# subd.net
KiCad netlist of a schematic drawn in EAGLE
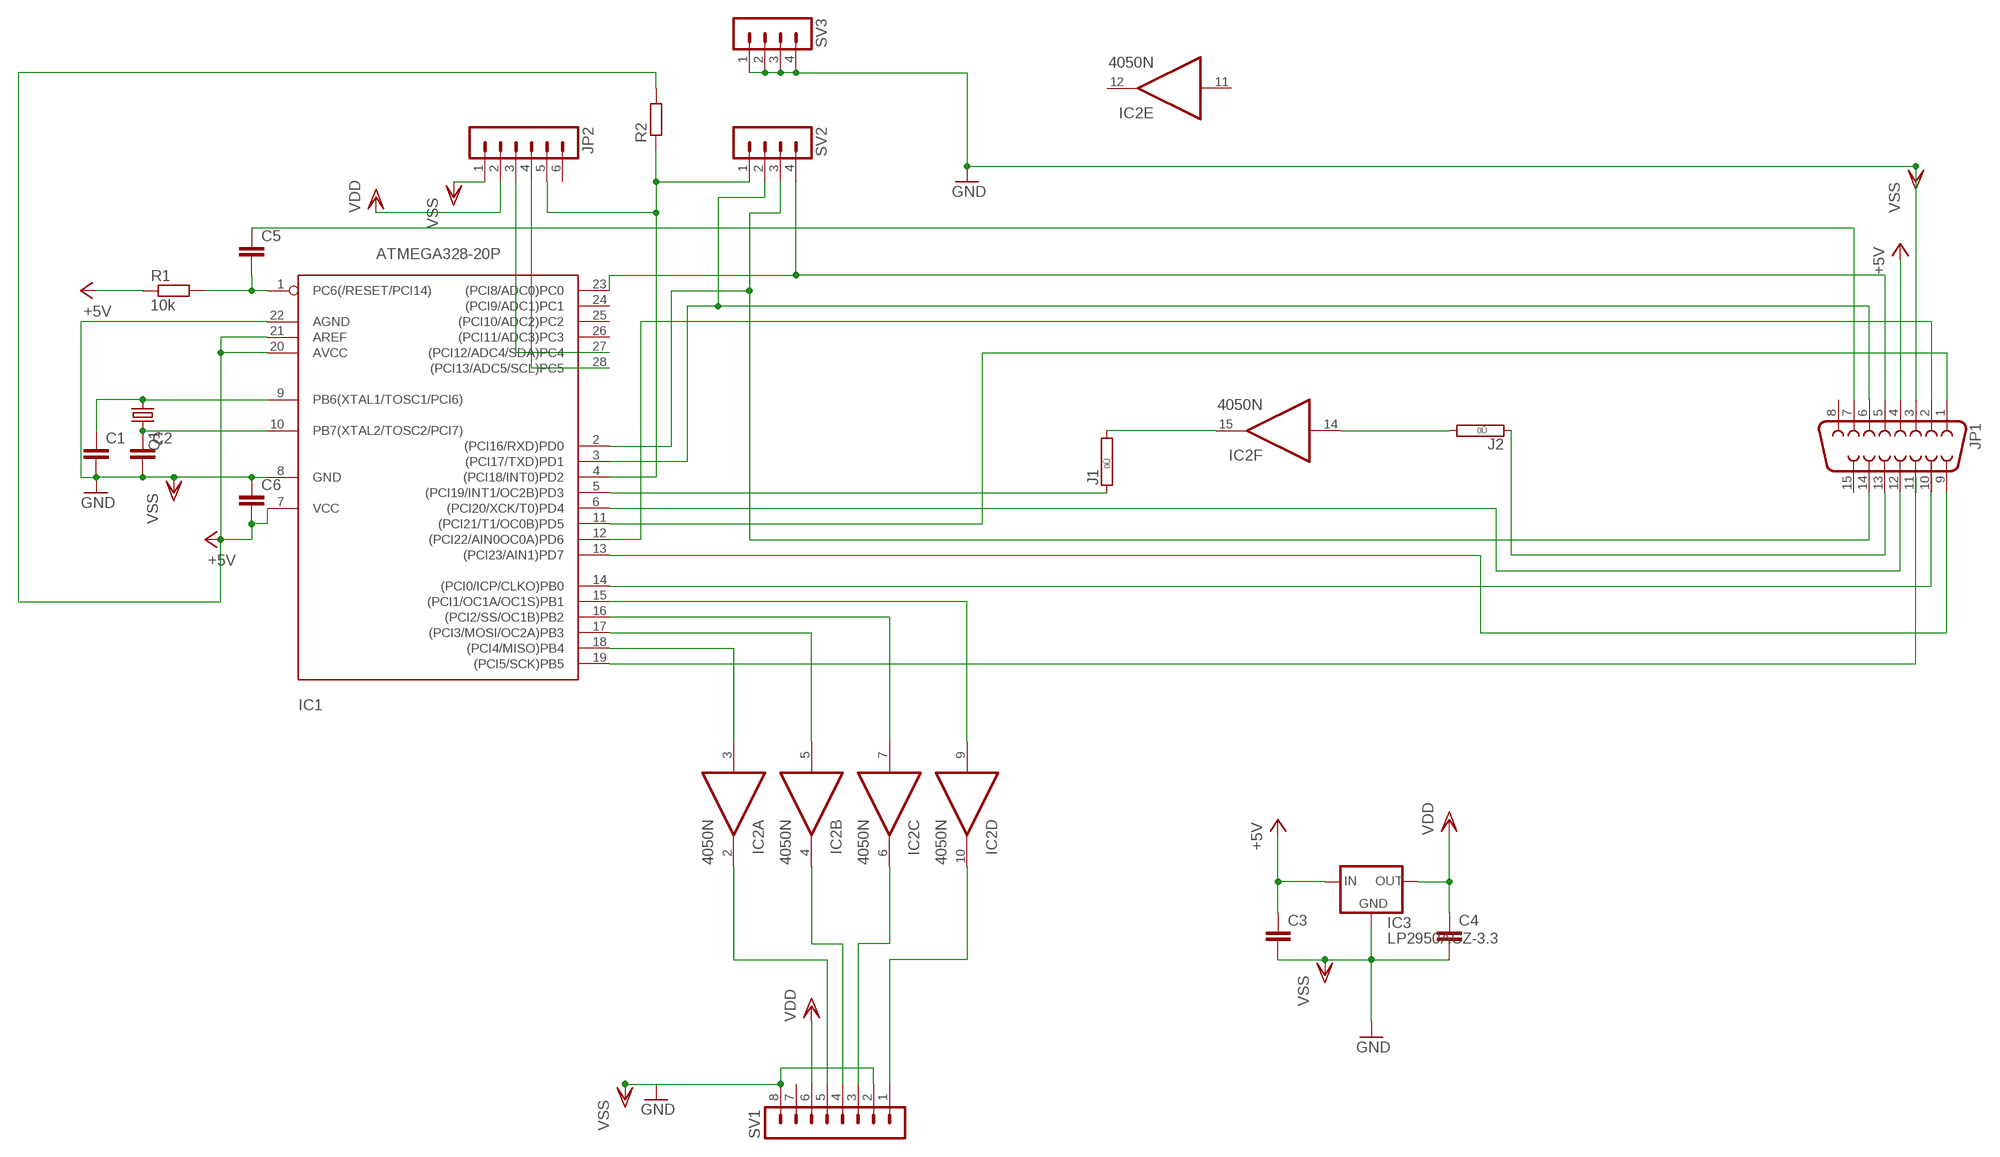
[diagram p0: schematic, sheet 1]

(export (version "E")
  (design (tool "Eeschema 10.0.6"))
  (components
    (comp (ref "C1")
      (value "C5/3")
      (footprint "eagle-import:C5B3")
      (libsource (lib "eagle-import") (part "C5/3"))
    )
    (comp (ref "C2")
      (value "C5/3")
      (footprint "eagle-import:C5B3")
      (libsource (lib "eagle-import") (part "C5/3"))
    )
    (comp (ref "C3")
      (value "C2.5/5")
      (footprint "eagle-import:C2.5-5")
      (libsource (lib "eagle-import") (part "C2.5/5"))
    )
    (comp (ref "C4")
      (value "C2.5/5")
      (footprint "eagle-import:C2.5-5")
      (libsource (lib "eagle-import") (part "C2.5/5"))
    )
    (comp (ref "C5")
      (value "C5/3")
      (footprint "eagle-import:C5B3")
      (libsource (lib "eagle-import") (part "C5/3"))
    )
    (comp (ref "C6")
      (value "C5/3")
      (footprint "eagle-import:C5B3")
      (libsource (lib "eagle-import") (part "C5/3"))
    )
    (comp (ref "IC1")
      (value "ATMEGA328-20P")
      (footprint "eagle-import:DIL28-3")
      (libsource (lib "eagle-import") (part "ATMEGA328P-20"))
    )
    (comp (ref "IC2")
      (value "4050N")
      (footprint "eagle-import:DIL16")
      (libsource (lib "eagle-import") (part "4050N"))
    )
    (comp (ref "IC3")
      (value "LP2950ACZ-3.3")
      (footprint "eagle-import:TO92")
      (libsource (lib "eagle-import") (part "LP2950?ACZ-3.3"))
    )
    (comp (ref "J1")
      (value "0R")
      (footprint "eagle-import:0R_10")
      (libsource (lib "eagle-import") (part "0R"))
    )
    (comp (ref "J2")
      (value "0R")
      (footprint "eagle-import:0R_10")
      (libsource (lib "eagle-import") (part "0R"))
    )
    (comp (ref "JP1")
      (value "F15H")
      (footprint "eagle-import:F15H")
      (libsource (lib "eagle-import") (part "F15H"))
    )
    (comp (ref "JP2")
      (value "MA06-1")
      (footprint "eagle-import:MA06-1")
      (libsource (lib "eagle-import") (part "MA06-1"))
    )
    (comp (ref "Q1")
      (value "CRYSTALHC18U-V")
      (footprint "eagle-import:HC18U-V")
      (libsource (lib "eagle-import") (part "CRYSTALHC18U-V"))
    )
    (comp (ref "R1")
      (value "10k")
      (footprint "eagle-import:0207_12")
      (libsource (lib "eagle-import") (part "R-EU_0207/12"))
    )
    (comp (ref "R2")
      (value "R-EU_0207/10")
      (footprint "eagle-import:0207_10")
      (libsource (lib "eagle-import") (part "R-EU_0207/10"))
    )
    (comp (ref "SV1")
      (value "MA08-1")
      (footprint "eagle-import:MA08-1")
      (libsource (lib "eagle-import") (part "MA08-1"))
    )
    (comp (ref "SV2")
      (value "MA04-1")
      (footprint "eagle-import:MA04-1")
      (libsource (lib "eagle-import") (part "MA04-1"))
    )
    (comp (ref "SV3")
      (value "MA04-1")
      (footprint "eagle-import:MA04-1")
      (libsource (lib "eagle-import") (part "MA04-1"))
    )
  )
  (nets
    (net (code "1") (name "+5V") (class "Default")
      (node (ref "C3") (pin "1") (pinfunction "1_1") (pintype "passive"))
      (node (ref "C6") (pin "2") (pinfunction "2_2") (pintype "passive"))
      (node (ref "IC1") (pin "20") (pinfunction "AVCC_20") (pintype "bidirectional"))
      (node (ref "IC1") (pin "21") (pinfunction "AREF_21") (pintype "bidirectional"))
      (node (ref "IC1") (pin "7") (pinfunction "VCC_7") (pintype "bidirectional"))
      (node (ref "IC3") (pin "3") (pinfunction "IN_3") (pintype "input"))
      (node (ref "JP1") (pin "4") (pinfunction "4_4") (pintype "passive"))
      (node (ref "R1") (pin "1") (pinfunction "1_1") (pintype "passive"))
      (node (ref "R2") (pin "2") (pinfunction "2_2") (pintype "passive"))
    )
    (net (code "2") (name "GND") (class "Default")
      (node (ref "C1") (pin "2") (pinfunction "2_2") (pintype "passive"))
      (node (ref "C2") (pin "2") (pinfunction "2_2") (pintype "passive"))
      (node (ref "C3") (pin "2") (pinfunction "2_2") (pintype "passive"))
      (node (ref "C4") (pin "2") (pinfunction "2_2") (pintype "passive"))
      (node (ref "C6") (pin "1") (pinfunction "1_1") (pintype "passive"))
      (node (ref "IC1") (pin "22") (pinfunction "AGND_22") (pintype "bidirectional"))
      (node (ref "IC1") (pin "8") (pinfunction "GND_8") (pintype "bidirectional"))
      (node (ref "IC3") (pin "2") (pinfunction "GND_2") (pintype "input"))
      (node (ref "JP1") (pin "3") (pinfunction "3_3") (pintype "passive"))
      (node (ref "JP2") (pin "1") (pinfunction "1_1") (pintype "passive"))
      (node (ref "SV1") (pin "2") (pinfunction "2_2") (pintype "passive"))
      (node (ref "SV1") (pin "8") (pinfunction "8_8") (pintype "passive"))
      (node (ref "SV3") (pin "1") (pinfunction "1_1") (pintype "passive"))
      (node (ref "SV3") (pin "2") (pinfunction "2_2") (pintype "passive"))
      (node (ref "SV3") (pin "3") (pinfunction "3_3") (pintype "passive"))
      (node (ref "SV3") (pin "4") (pinfunction "4_4") (pintype "passive"))
    )
    (net (code "3") (name "Net-(C5-Pad1)") (class "Default")
      (node (ref "C5") (pin "1") (pinfunction "1_1") (pintype "passive"))
      (node (ref "JP1") (pin "7") (pinfunction "7_7") (pintype "passive"))
    )
    (net (code "4") (name "Net-(IC1-(PCI0{slash}ICP{slash}CLKO)PB0)") (class "Default")
      (node (ref "IC1") (pin "14") (pinfunction "(PCI0/ICP/CLKO)PB0_14") (pintype "bidirectional"))
      (node (ref "JP1") (pin "10") (pinfunction "10_10") (pintype "passive"))
    )
    (net (code "5") (name "Net-(IC1-(PCI1{slash}OC1A{slash}OC1S)PB1)") (class "Default")
      (node (ref "IC1") (pin "15") (pinfunction "(PCI1/OC1A/OC1S)PB1_15") (pintype "bidirectional"))
      (node (ref "IC2") (pin "9") (pinfunction "I_9") (pintype "input"))
    )
    (net (code "6") (name "Net-(IC1-(PCI2{slash}SS{slash}OC1B)PB2)") (class "Default")
      (node (ref "IC1") (pin "16") (pinfunction "(PCI2/SS/OC1B)PB2_16") (pintype "bidirectional"))
      (node (ref "IC2") (pin "7") (pinfunction "I_7") (pintype "input"))
    )
    (net (code "7") (name "Net-(IC1-(PCI3{slash}MOSI{slash}OC2A)PB3)") (class "Default")
      (node (ref "IC1") (pin "17") (pinfunction "(PCI3/MOSI/OC2A)PB3_17") (pintype "bidirectional"))
      (node (ref "IC2") (pin "5") (pinfunction "I_5") (pintype "input"))
    )
    (net (code "8") (name "Net-(IC1-(PCI4{slash}MISO)PB4)") (class "Default")
      (node (ref "IC1") (pin "18") (pinfunction "(PCI4/MISO)PB4_18") (pintype "bidirectional"))
      (node (ref "IC2") (pin "3") (pinfunction "I_3") (pintype "input"))
    )
    (net (code "9") (name "Net-(IC1-(PCI5{slash}SCK)PB5)") (class "Default")
      (node (ref "IC1") (pin "19") (pinfunction "(PCI5/SCK)PB5_19") (pintype "bidirectional"))
      (node (ref "JP1") (pin "11") (pinfunction "11_11") (pintype "passive"))
    )
    (net (code "10") (name "Net-(IC1-(PCI8{slash}ADC0)PC0)") (class "Default")
      (node (ref "IC1") (pin "23") (pinfunction "(PCI8/ADC0)PC0_23") (pintype "bidirectional"))
      (node (ref "JP1") (pin "5") (pinfunction "5_5") (pintype "passive"))
      (node (ref "SV2") (pin "4") (pinfunction "4_4") (pintype "passive"))
    )
    (net (code "11") (name "Net-(IC1-(PCI12{slash}ADC4{slash}SDA)PC4)") (class "Default")
      (node (ref "IC1") (pin "27") (pinfunction "(PCI12/ADC4/SDA)PC4_27") (pintype "bidirectional"))
      (node (ref "JP2") (pin "3") (pinfunction "3_3") (pintype "passive"))
    )
    (net (code "12") (name "Net-(IC1-(PCI13{slash}ADC5{slash}SCL)PC5)") (class "Default")
      (node (ref "IC1") (pin "28") (pinfunction "(PCI13/ADC5/SCL)PC5_28") (pintype "bidirectional"))
      (node (ref "JP2") (pin "4") (pinfunction "4_4") (pintype "passive"))
    )
    (net (code "13") (name "Net-(IC1-(PCI16{slash}RXD)PD0)") (class "Default")
      (node (ref "IC1") (pin "2") (pinfunction "(PCI16/RXD)PD0_2") (pintype "bidirectional"))
      (node (ref "JP1") (pin "14") (pinfunction "14_14") (pintype "passive"))
      (node (ref "SV2") (pin "3") (pinfunction "3_3") (pintype "passive"))
    )
    (net (code "14") (name "Net-(IC1-(PCI17{slash}TXD)PD1)") (class "Default")
      (node (ref "IC1") (pin "3") (pinfunction "(PCI17/TXD)PD1_3") (pintype "bidirectional"))
      (node (ref "JP1") (pin "6") (pinfunction "6_6") (pintype "passive"))
      (node (ref "SV2") (pin "2") (pinfunction "2_2") (pintype "passive"))
    )
    (net (code "15") (name "Net-(IC1-(PCI18{slash}INT0)PD2)") (class "Default")
      (node (ref "IC1") (pin "4") (pinfunction "(PCI18/INT0)PD2_4") (pintype "bidirectional"))
      (node (ref "JP2") (pin "5") (pinfunction "5_5") (pintype "passive"))
      (node (ref "R2") (pin "1") (pinfunction "1_1") (pintype "passive"))
      (node (ref "SV2") (pin "1") (pinfunction "1_1") (pintype "passive"))
    )
    (net (code "16") (name "Net-(IC1-(PCI19{slash}INT1{slash}OC2B)PD3)") (class "Default")
      (node (ref "IC1") (pin "5") (pinfunction "(PCI19/INT1/OC2B)PD3_5") (pintype "bidirectional"))
      (node (ref "J1") (pin "1") (pinfunction "1_1") (pintype "passive"))
    )
    (net (code "17") (name "Net-(IC1-(PCI20{slash}XCK{slash}T0)PD4)") (class "Default")
      (node (ref "IC1") (pin "6") (pinfunction "(PCI20/XCK/T0)PD4_6") (pintype "bidirectional"))
      (node (ref "JP1") (pin "12") (pinfunction "12_12") (pintype "passive"))
    )
    (net (code "18") (name "Net-(IC1-(PCI21{slash}T1{slash}OC0B)PD5)") (class "Default")
      (node (ref "IC1") (pin "11") (pinfunction "(PCI21/T1/OC0B)PD5_11") (pintype "bidirectional"))
      (node (ref "JP1") (pin "1") (pinfunction "1_1") (pintype "passive"))
    )
    (net (code "19") (name "Net-(IC1-(PCI22{slash}AIN0OC0A)PD6)") (class "Default")
      (node (ref "IC1") (pin "12") (pinfunction "(PCI22/AIN0OC0A)PD6_12") (pintype "bidirectional"))
      (node (ref "JP1") (pin "2") (pinfunction "2_2") (pintype "passive"))
    )
    (net (code "20") (name "Net-(IC1-(PCI23{slash}AIN1)PD7)") (class "Default")
      (node (ref "IC1") (pin "13") (pinfunction "(PCI23/AIN1)PD7_13") (pintype "bidirectional"))
      (node (ref "JP1") (pin "9") (pinfunction "9_9") (pintype "passive"))
    )
    (net (code "21") (name "Net-(IC1-PB6(XTAL1{slash}TOSC1{slash}PCI6))") (class "Default")
      (node (ref "C1") (pin "1") (pinfunction "1_1") (pintype "passive"))
      (node (ref "IC1") (pin "9") (pinfunction "PB6(XTAL1/TOSC1/PCI6)_9") (pintype "bidirectional"))
      (node (ref "Q1") (pin "1") (pinfunction "1_1") (pintype "passive"))
    )
    (net (code "22") (name "Net-(IC1-PB7(XTAL2{slash}TOSC2{slash}PCI7))") (class "Default")
      (node (ref "C2") (pin "1") (pinfunction "1_1") (pintype "passive"))
      (node (ref "IC1") (pin "10") (pinfunction "PB7(XTAL2/TOSC2/PCI7)_10") (pintype "bidirectional"))
      (node (ref "Q1") (pin "2") (pinfunction "2_2") (pintype "passive"))
    )
    (net (code "23") (name "Net-(IC1-PC6({slash}RESET{slash}PCI14))") (class "Default")
      (node (ref "C5") (pin "2") (pinfunction "2_2") (pintype "passive"))
      (node (ref "IC1") (pin "1") (pinfunction "PC6(/RESET/PCI14)_1") (pintype "bidirectional"))
      (node (ref "R1") (pin "2") (pinfunction "2_2") (pintype "passive"))
    )
    (net (code "24") (name "Net-(IC2A-O)") (class "Default")
      (node (ref "IC2") (pin "2") (pinfunction "O_2") (pintype "output"))
      (node (ref "SV1") (pin "5") (pinfunction "5_5") (pintype "passive"))
    )
    (net (code "25") (name "Net-(IC2B-O)") (class "Default")
      (node (ref "IC2") (pin "4") (pinfunction "O_4") (pintype "output"))
      (node (ref "SV1") (pin "4") (pinfunction "4_4") (pintype "passive"))
    )
    (net (code "26") (name "Net-(IC2C-O)") (class "Default")
      (node (ref "IC2") (pin "6") (pinfunction "O_6") (pintype "output"))
      (node (ref "SV1") (pin "3") (pinfunction "3_3") (pintype "passive"))
    )
    (net (code "27") (name "Net-(IC2D-O)") (class "Default")
      (node (ref "IC2") (pin "10") (pinfunction "O_10") (pintype "output"))
      (node (ref "SV1") (pin "1") (pinfunction "1_1") (pintype "passive"))
    )
    (net (code "28") (name "Net-(IC2F-I)") (class "Default")
      (node (ref "IC2") (pin "14") (pinfunction "I_14") (pintype "input"))
      (node (ref "J2") (pin "2") (pinfunction "2_2") (pintype "passive"))
    )
    (net (code "29") (name "Net-(IC2F-O)") (class "Default")
      (node (ref "IC2") (pin "15") (pinfunction "O_15") (pintype "output"))
      (node (ref "J1") (pin "2") (pinfunction "2_2") (pintype "passive"))
    )
    (net (code "30") (name "Net-(J2-Pad1)") (class "Default")
      (node (ref "J2") (pin "1") (pinfunction "1_1") (pintype "passive"))
      (node (ref "JP1") (pin "13") (pinfunction "13_13") (pintype "passive"))
    )
    (net (code "31") (name "VDD") (class "Default")
      (node (ref "C4") (pin "1") (pinfunction "1_1") (pintype "passive"))
      (node (ref "IC3") (pin "1") (pinfunction "OUT_1") (pintype "passive"))
      (node (ref "JP2") (pin "2") (pinfunction "2_2") (pintype "passive"))
      (node (ref "SV1") (pin "6") (pinfunction "6_6") (pintype "passive"))
    )
    (net (code "32") (name "unconnected-(IC1-(PCI9{slash}ADC1)PC1-Pad24)") (class "Default")
      (node (ref "IC1") (pin "24") (pinfunction "(PCI9/ADC1)PC1_24") (pintype "bidirectional"))
    )
    (net (code "33") (name "unconnected-(IC1-(PCI10{slash}ADC2)PC2-Pad25)") (class "Default")
      (node (ref "IC1") (pin "25") (pinfunction "(PCI10/ADC2)PC2_25") (pintype "bidirectional"))
    )
    (net (code "34") (name "unconnected-(IC1-(PCI11{slash}ADC3)PC3-Pad26)") (class "Default")
      (node (ref "IC1") (pin "26") (pinfunction "(PCI11/ADC3)PC3_26") (pintype "bidirectional"))
    )
    (net (code "35") (name "unconnected-(IC2E-I-Pad11)") (class "Default")
      (node (ref "IC2") (pin "11") (pinfunction "I_11") (pintype "input"))
    )
    (net (code "36") (name "unconnected-(IC2E-O-Pad12)") (class "Default")
      (node (ref "IC2") (pin "12") (pinfunction "O_12") (pintype "output"))
    )
    (net (code "37") (name "unconnected-(JP1-Pad8)") (class "Default")
      (node (ref "JP1") (pin "8") (pinfunction "8_8") (pintype "passive"))
    )
    (net (code "38") (name "unconnected-(JP1-Pad15)") (class "Default")
      (node (ref "JP1") (pin "15") (pinfunction "15_15") (pintype "passive"))
    )
    (net (code "39") (name "unconnected-(JP2-Pad6)") (class "Default")
      (node (ref "JP2") (pin "6") (pinfunction "6_6") (pintype "passive"))
    )
    (net (code "40") (name "unconnected-(SV1-Pad7)") (class "Default")
      (node (ref "SV1") (pin "7") (pinfunction "7_7") (pintype "passive"))
    )
  )
)
